# usb_uart_converter.net
KiCad netlist of a schematic drawn in Altium Designer
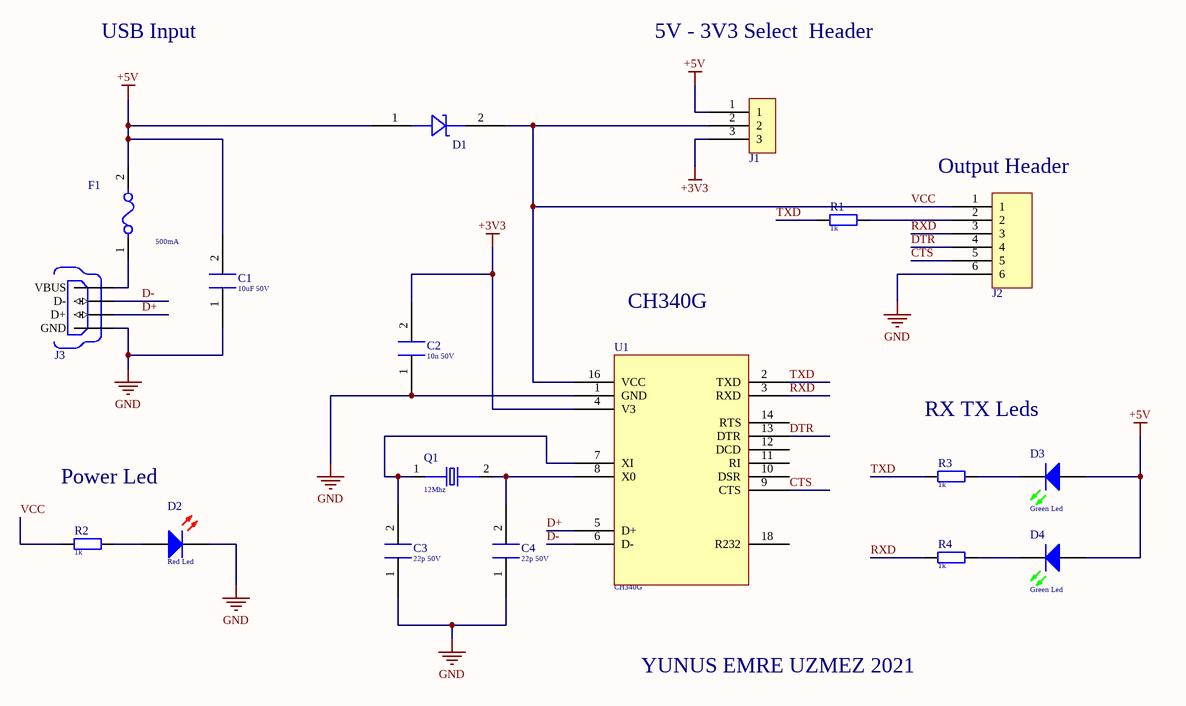
[diagram p0: usb_uart_converter.SchDoc]

(export (version "E")
  (design (tool "Eeschema 10.0.6"))
  (components
    (comp (ref "C1")
      (value "10uF 50V")
      (footprint "CAP 0805")
      (fields (field (name "Comment") "10uF C0805"))
      (libsource (lib "usb_uart_converter") (part "10uF C0805"))
    )
    (comp (ref "C2")
      (value "10n 50V")
      (footprint "CAP 0805")
      (fields (field (name "Comment") "10n C0805"))
      (libsource (lib "usb_uart_converter") (part "10n C0805"))
    )
    (comp (ref "C3")
      (value "22p 50V")
      (footprint "CAP 0805")
      (fields (field (name "Comment") "22p C0805"))
      (libsource (lib "usb_uart_converter") (part "22p C0805"))
    )
    (comp (ref "C4")
      (value "22p 50V")
      (footprint "CAP 0805")
      (fields (field (name "Comment") "22p C0805"))
      (libsource (lib "usb_uart_converter") (part "22p C0805"))
    )
    (comp (ref "D1")
      (value "MMSZ4668T1G")
      (footprint "SOD-123")
      (libsource (lib "usb_uart_converter") (part "MMSZ4668T1G"))
    )
    (comp (ref "D2")
      (value "Led Red")
      (footprint "LED RED 0805")
      (fields (field (name "NAME") "Red Led"))
      (libsource (lib "usb_uart_converter") (part "Led Red"))
    )
    (comp (ref "D3")
      (value "Led Green")
      (footprint "LED GREEN 0805")
      (fields (field (name "NAME") "Green Led"))
      (libsource (lib "usb_uart_converter") (part "Led Green"))
    )
    (comp (ref "D4")
      (value "Led Green")
      (footprint "LED GREEN 0805")
      (fields (field (name "NAME") "Green Led"))
      (libsource (lib "usb_uart_converter") (part "Led Green"))
    )
    (comp (ref "F1")
      (value "500mA")
      (footprint "FUSE")
      (fields (field (name "Comment") "0.5A Fuse"))
      (libsource (lib "usb_uart_converter") (part "0.5A Fuse"))
    )
    (comp (ref "J1")
      (value "1x3 Header")
      (footprint "1x3 HEADER")
      (libsource (lib "usb_uart_converter") (part "1x3 Header"))
    )
    (comp (ref "J2")
      (value "Header 1x6")
      (footprint "1X6 HEADER")
      (libsource (lib "usb_uart_converter") (part "Header 1x6"))
    )
    (comp (ref "J3")
      (value "USB")
      (footprint "USB TYPE A")
      (libsource (lib "usb_uart_converter") (part "USB"))
    )
    (comp (ref "Q1")
      (value "12Mhz")
      (footprint "OSCILLATOR")
      (fields (field (name "Comment") "12 MHz Oscillator"))
      (libsource (lib "usb_uart_converter") (part "12 MHz Oscillator"))
    )
    (comp (ref "R1")
      (value "1k")
      (footprint "RES 0805")
      (fields (field (name "Comment") "0.33K R0805"))
      (libsource (lib "usb_uart_converter") (part "0.33K R0805"))
    )
    (comp (ref "R2")
      (value "1k")
      (footprint "RES 0805")
      (fields (field (name "Comment") "0.33K R0805"))
      (libsource (lib "usb_uart_converter") (part "0.33K R0805"))
    )
    (comp (ref "R3")
      (value "1k")
      (footprint "RES 0805")
      (fields (field (name "Comment") "0.33K R0805"))
      (libsource (lib "usb_uart_converter") (part "0.33K R0805"))
    )
    (comp (ref "R4")
      (value "1k")
      (footprint "RES 0805")
      (fields (field (name "Comment") "0.33K R0805"))
      (libsource (lib "usb_uart_converter") (part "0.33K R0805"))
    )
    (comp (ref "U1")
      (value "CH340G")
      (footprint "SOP-16")
      (fields (field (name "NAME") "CH340G"))
      (libsource (lib "usb_uart_converter") (part "CH340G"))
    )
  )
  (nets
    (net (code "1") (name "+3V3") (class "Default")
      (node (ref "C2") (pin "2") (pinfunction "8_2") (pintype "passive"))
      (node (ref "J1") (pin "3") (pinfunction "3_3") (pintype "passive"))
      (node (ref "U1") (pin "4") (pinfunction "V3_4") (pintype "passive"))
    )
    (net (code "2") (name "+5V") (class "Default")
      (node (ref "C1") (pin "2") (pinfunction "8_2") (pintype "passive"))
      (node (ref "D1") (pin "1") (pinfunction "12_1") (pintype "passive"))
      (node (ref "D3") (pin "1") (pinfunction "A_1") (pintype "passive"))
      (node (ref "D4") (pin "1") (pinfunction "A_1") (pintype "passive"))
      (node (ref "F1") (pin "2") (pinfunction "2_2") (pintype "passive"))
      (node (ref "J1") (pin "1") (pinfunction "1_1") (pintype "passive"))
    )
    (net (code "3") (name "/CTS") (class "Default")
      (node (ref "J2") (pin "5") (pinfunction "5_5") (pintype "passive"))
      (node (ref "U1") (pin "9") (pinfunction "CTS_9") (pintype "passive"))
    )
    (net (code "4") (name "/D+") (class "Default")
      (node (ref "J3") (pin "3") (pinfunction "D+_3") (pintype "bidirectional"))
      (node (ref "U1") (pin "5") (pinfunction "D+_5") (pintype "passive"))
    )
    (net (code "5") (name "/D-") (class "Default")
      (node (ref "J3") (pin "2") (pinfunction "D-_2") (pintype "bidirectional"))
      (node (ref "U1") (pin "6") (pinfunction "D-_6") (pintype "passive"))
    )
    (net (code "6") (name "/DTR") (class "Default")
      (node (ref "J2") (pin "4") (pinfunction "4_4") (pintype "passive"))
      (node (ref "U1") (pin "13") (pinfunction "DTR_13") (pintype "passive"))
    )
    (net (code "7") (name "/RXD") (class "Default")
      (node (ref "J2") (pin "3") (pinfunction "3_3") (pintype "passive"))
      (node (ref "R4") (pin "1") (pinfunction "1_1") (pintype "passive"))
      (node (ref "U1") (pin "3") (pinfunction "RXD_3") (pintype "passive"))
    )
    (net (code "8") (name "/TXD") (class "Default")
      (node (ref "R1") (pin "1") (pinfunction "1_1") (pintype "passive"))
      (node (ref "R3") (pin "1") (pinfunction "1_1") (pintype "passive"))
      (node (ref "U1") (pin "2") (pinfunction "TXD_2") (pintype "passive"))
    )
    (net (code "9") (name "/VCC") (class "Default")
      (node (ref "D1") (pin "2") (pinfunction "11_2") (pintype "passive"))
      (node (ref "J1") (pin "2") (pinfunction "2_2") (pintype "passive"))
      (node (ref "J2") (pin "1") (pinfunction "1_1") (pintype "passive"))
      (node (ref "R2") (pin "1") (pinfunction "1_1") (pintype "passive"))
      (node (ref "U1") (pin "16") (pinfunction "VCC_16") (pintype "passive"))
    )
    (net (code "10") (name "GND") (class "Default")
      (node (ref "C1") (pin "1") (pinfunction "9_1") (pintype "passive"))
      (node (ref "C2") (pin "1") (pinfunction "9_1") (pintype "passive"))
      (node (ref "C3") (pin "1") (pinfunction "9_1") (pintype "passive"))
      (node (ref "C4") (pin "1") (pinfunction "9_1") (pintype "passive"))
      (node (ref "D2") (pin "2") (pinfunction "K_2") (pintype "passive"))
      (node (ref "J2") (pin "6") (pinfunction "6_6") (pintype "passive"))
      (node (ref "J3") (pin "4") (pinfunction "GND_4") (pintype "power_in"))
      (node (ref "U1") (pin "1") (pinfunction "GND_1") (pintype "passive"))
    )
    (net (code "11") (name "Net-(C3-8)") (class "Default")
      (node (ref "C3") (pin "2") (pinfunction "8_2") (pintype "passive"))
      (node (ref "Q1") (pin "1") (pinfunction "1_1") (pintype "passive"))
      (node (ref "U1") (pin "7") (pinfunction "XI_7") (pintype "passive"))
    )
    (net (code "12") (name "Net-(C4-8)") (class "Default")
      (node (ref "C4") (pin "2") (pinfunction "8_2") (pintype "passive"))
      (node (ref "Q1") (pin "2") (pinfunction "2_2") (pintype "passive"))
      (node (ref "U1") (pin "8") (pinfunction "X0_8") (pintype "passive"))
    )
    (net (code "13") (name "Net-(D2-A)") (class "Default")
      (node (ref "D2") (pin "1") (pinfunction "A_1") (pintype "passive"))
      (node (ref "R2") (pin "2") (pinfunction "2_2") (pintype "passive"))
    )
    (net (code "14") (name "Net-(D3-K)") (class "Default")
      (node (ref "D3") (pin "2") (pinfunction "K_2") (pintype "passive"))
      (node (ref "R3") (pin "2") (pinfunction "2_2") (pintype "passive"))
    )
    (net (code "15") (name "Net-(D4-K)") (class "Default")
      (node (ref "D4") (pin "2") (pinfunction "K_2") (pintype "passive"))
      (node (ref "R4") (pin "2") (pinfunction "2_2") (pintype "passive"))
    )
    (net (code "16") (name "Net-(J2-Pad2)") (class "Default")
      (node (ref "J2") (pin "2") (pinfunction "2_2") (pintype "passive"))
      (node (ref "R1") (pin "2") (pinfunction "2_2") (pintype "passive"))
    )
    (net (code "17") (name "Net-(J3-VBUS)") (class "Default")
      (node (ref "F1") (pin "1") (pinfunction "1_1") (pintype "passive"))
      (node (ref "J3") (pin "1") (pinfunction "VBUS_1") (pintype "power_in"))
    )
    (net (code "18") (name "unconnected-(U1-DCD-Pad12)") (class "Default")
      (node (ref "U1") (pin "12") (pinfunction "DCD_12") (pintype "passive"))
    )
    (net (code "19") (name "unconnected-(U1-DSR-Pad10)") (class "Default")
      (node (ref "U1") (pin "10") (pinfunction "DSR_10") (pintype "passive"))
    )
    (net (code "20") (name "unconnected-(U1-R232-Pad18)") (class "Default")
      (node (ref "U1") (pin "18") (pinfunction "R232_18") (pintype "passive"))
    )
    (net (code "21") (name "unconnected-(U1-RI-Pad11)") (class "Default")
      (node (ref "U1") (pin "11") (pinfunction "RI_11") (pintype "passive"))
    )
    (net (code "22") (name "unconnected-(U1-RTS-Pad14)") (class "Default")
      (node (ref "U1") (pin "14") (pinfunction "RTS_14") (pintype "passive"))
    )
  )
)
